# RS485_converter.net
KiCad netlist of a schematic drawn in EAGLE
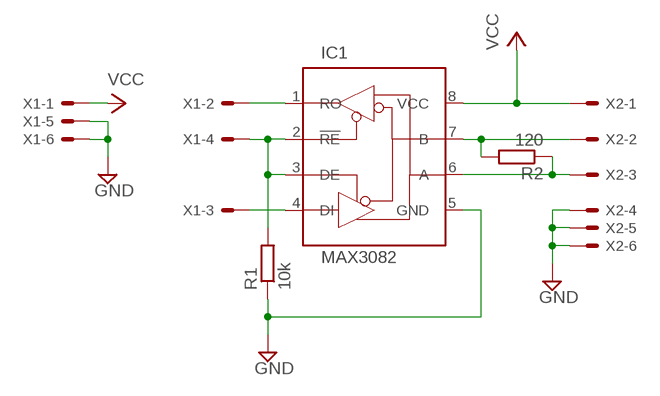
[diagram p0: schematic, sheet 1]

(export (version "E")
  (design (tool "Eeschema 10.0.6"))
  (components
    (comp (ref "IC1")
      (value "MAX3082")
      (footprint "eagle-import:DIL08")
      (libsource (lib "eagle-import") (part "MAX3082CPD"))
    )
    (comp (ref "R1")
      (value "10k")
      (footprint "eagle-import:0207_12")
      (libsource (lib "eagle-import") (part "R-EU_0207/12"))
    )
    (comp (ref "R2")
      (value "120")
      (footprint "eagle-import:0207_12")
      (libsource (lib "eagle-import") (part "R-EU_0207/12"))
    )
    (comp (ref "X1")
      (value "332-06")
      (footprint "eagle-import:332-06")
      (libsource (lib "eagle-import") (part "332-06"))
    )
    (comp (ref "X2")
      (value "332-06")
      (footprint "eagle-import:332-06")
      (libsource (lib "eagle-import") (part "332-06"))
    )
  )
  (nets
    (net (code "1") (name "GND") (class "Default")
      (node (ref "IC1") (pin "5") (pinfunction "GND_5") (pintype "input"))
      (node (ref "R1") (pin "1") (pinfunction "1_1") (pintype "passive"))
      (node (ref "X1") (pin "5") (pinfunction "S_5") (pintype "passive"))
      (node (ref "X1") (pin "6") (pinfunction "S_6") (pintype "passive"))
      (node (ref "X2") (pin "4") (pinfunction "S_4") (pintype "passive"))
      (node (ref "X2") (pin "5") (pinfunction "S_5") (pintype "passive"))
      (node (ref "X2") (pin "6") (pinfunction "S_6") (pintype "passive"))
    )
    (net (code "2") (name "Net-(IC1-A)") (class "Default")
      (node (ref "IC1") (pin "6") (pinfunction "A_6") (pintype "input"))
      (node (ref "R2") (pin "1") (pinfunction "1_1") (pintype "passive"))
      (node (ref "X2") (pin "3") (pinfunction "S_3") (pintype "passive"))
    )
    (net (code "3") (name "Net-(IC1-B)") (class "Default")
      (node (ref "IC1") (pin "7") (pinfunction "B_7") (pintype "output"))
      (node (ref "R2") (pin "2") (pinfunction "2_2") (pintype "passive"))
      (node (ref "X2") (pin "2") (pinfunction "S_2") (pintype "passive"))
    )
    (net (code "4") (name "Net-(IC1-DE)") (class "Default")
      (node (ref "IC1") (pin "2") (pinfunction "~{RE}_2") (pintype "input"))
      (node (ref "IC1") (pin "3") (pinfunction "DE_3") (pintype "input"))
      (node (ref "R1") (pin "2") (pinfunction "2_2") (pintype "passive"))
      (node (ref "X1") (pin "4") (pinfunction "S_4") (pintype "passive"))
    )
    (net (code "5") (name "Net-(IC1-DI)") (class "Default")
      (node (ref "IC1") (pin "4") (pinfunction "DI_4") (pintype "input"))
      (node (ref "X1") (pin "3") (pinfunction "S_3") (pintype "passive"))
    )
    (net (code "6") (name "Net-(IC1-RO)") (class "Default")
      (node (ref "IC1") (pin "1") (pinfunction "RO_1") (pintype "output"))
      (node (ref "X1") (pin "2") (pinfunction "S_2") (pintype "passive"))
    )
    (net (code "7") (name "VCC") (class "Default")
      (node (ref "IC1") (pin "8") (pinfunction "VCC_8") (pintype "output"))
      (node (ref "X1") (pin "1") (pinfunction "S_1") (pintype "passive"))
      (node (ref "X2") (pin "1") (pinfunction "S_1") (pintype "passive"))
    )
  )
)
